# fpga-bank2-inside.net
KiCad netlist of a schematic drawn in Altium Designer
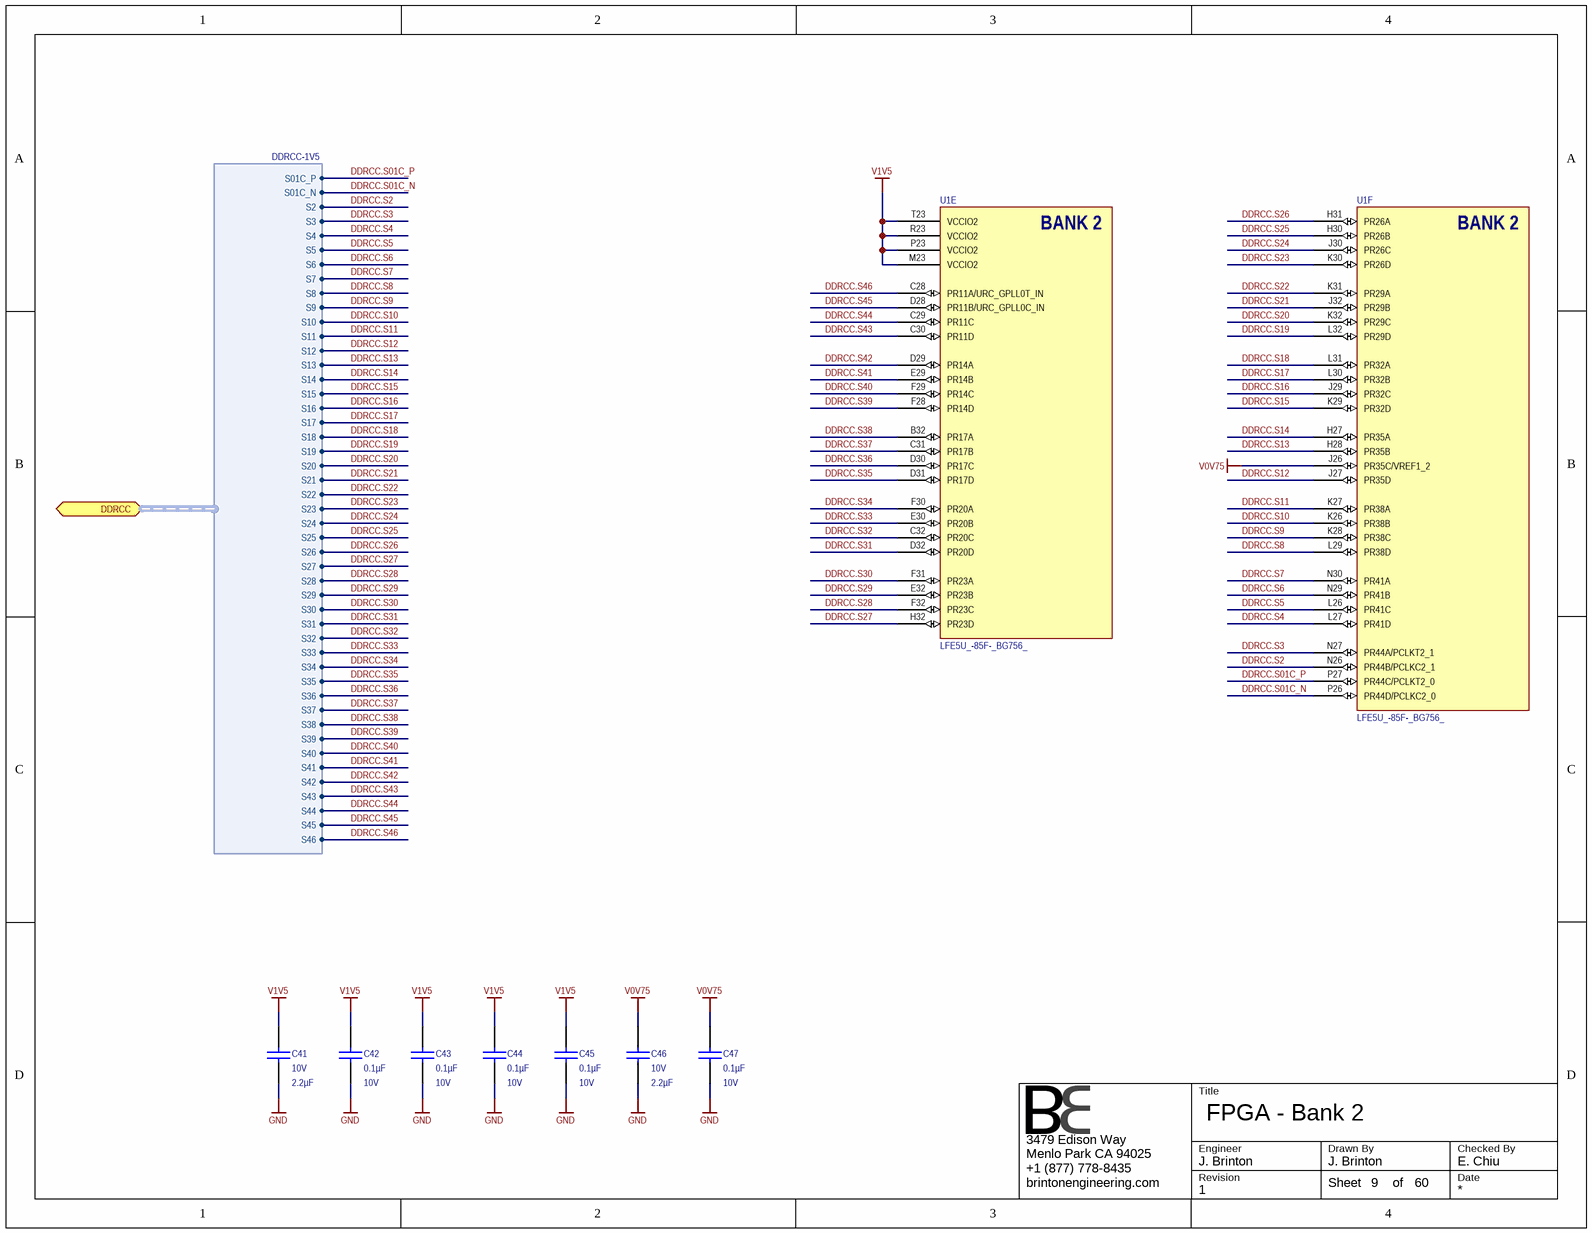
[diagram p0: fpga-bank2-inside.SchDoc]

(export (version "E")
  (design (tool "Eeschema 10.0.6"))
  (components
    (comp (ref "C41")
      (value "GRM188R71A225KE15D")
      (footprint "CAPC1608X90N")
      (description "CAP CER 2.2UF 10V 10% X7R 0603")
      (fields
        (field (name "MANUFACTURER") "Murata Electronics North America")
        (field (name "TOLERANCE") "±10%")
        (field (name "VOLTAGE - RATED") "10V")
        (field (name "CAPACITANCE") "2.2µF")
      )
      (libsource (lib "murata") (part "GRM188R71A225KE15D"))
    )
    (comp (ref "C42")
      (value "GRM155R71A104KA01J")
      (footprint "CAPC1005X56N")
      (description "CAP CER 0.1UF 10V 10% X7R 0402")
      (fields
        (field (name "MANUFACTURER") "Murata Electronics North America")
        (field (name "TOLERANCE") "±10%")
        (field (name "CAPACITANCE") "0.1µF")
        (field (name "VOLTAGE - RATED") "10V")
      )
      (libsource (lib "murata") (part "GRM155R71A104KA01J"))
    )
    (comp (ref "C43")
      (value "GRM155R71A104KA01J")
      (footprint "CAPC1005X56N")
      (description "CAP CER 0.1UF 10V 10% X7R 0402")
      (fields
        (field (name "MANUFACTURER") "Murata Electronics North America")
        (field (name "TOLERANCE") "±10%")
        (field (name "CAPACITANCE") "0.1µF")
        (field (name "VOLTAGE - RATED") "10V")
      )
      (libsource (lib "murata") (part "GRM155R71A104KA01J"))
    )
    (comp (ref "C44")
      (value "GRM155R71A104KA01J")
      (footprint "CAPC1005X56N")
      (description "CAP CER 0.1UF 10V 10% X7R 0402")
      (fields
        (field (name "MANUFACTURER") "Murata Electronics North America")
        (field (name "TOLERANCE") "±10%")
        (field (name "CAPACITANCE") "0.1µF")
        (field (name "VOLTAGE - RATED") "10V")
      )
      (libsource (lib "murata") (part "GRM155R71A104KA01J"))
    )
    (comp (ref "C45")
      (value "GRM155R71A104KA01J")
      (footprint "CAPC1005X56N")
      (description "CAP CER 0.1UF 10V 10% X7R 0402")
      (fields
        (field (name "MANUFACTURER") "Murata Electronics North America")
        (field (name "TOLERANCE") "±10%")
        (field (name "CAPACITANCE") "0.1µF")
        (field (name "VOLTAGE - RATED") "10V")
      )
      (libsource (lib "murata") (part "GRM155R71A104KA01J"))
    )
    (comp (ref "C46")
      (value "GRM188R71A225KE15D")
      (footprint "CAPC1608X90N")
      (description "CAP CER 2.2UF 10V 10% X7R 0603")
      (fields
        (field (name "MANUFACTURER") "Murata Electronics North America")
        (field (name "TOLERANCE") "±10%")
        (field (name "VOLTAGE - RATED") "10V")
        (field (name "CAPACITANCE") "2.2µF")
      )
      (libsource (lib "murata") (part "GRM188R71A225KE15D"))
    )
    (comp (ref "C47")
      (value "GRM155R71A104KA01J")
      (footprint "CAPC1005X56N")
      (description "CAP CER 0.1UF 10V 10% X7R 0402")
      (fields
        (field (name "MANUFACTURER") "Murata Electronics North America")
        (field (name "TOLERANCE") "±10%")
        (field (name "CAPACITANCE") "0.1µF")
        (field (name "VOLTAGE - RATED") "10V")
      )
      (libsource (lib "murata") (part "GRM155R71A104KA01J"))
    )
    (comp (ref "U1")
      (value "LFE5U_-85F-_BG756_")
      (footprint "lattice:caBGA756")
      (description "ECP5 FPGA, 85k LUT, 756-caBGA")
      (fields (field (name "MANUFACTURER") "Lattice Semiconductor"))
      (libsource (lib "lattice") (part "LFE5U_-85F-_BG756_"))
    )
  )
  (nets
    (net (code "2") (name "/DDRCC.S01C_N") (class "Default")
      (node (ref "U1") (pin "P26") (pinfunction "PR44D/PCLKC2_0_P26") (pintype "bidirectional"))
    )
    (net (code "3") (name "/DDRCC.S01C_P") (class "Default")
      (node (ref "U1") (pin "P27") (pinfunction "PR44C/PCLKT2_0_P27") (pintype "bidirectional"))
    )
    (net (code "4") (name "/DDRCC.S2") (class "Default")
      (node (ref "U1") (pin "N26") (pinfunction "PR44B/PCLKC2_1_N26") (pintype "bidirectional"))
    )
    (net (code "5") (name "/DDRCC.S3") (class "Default")
      (node (ref "U1") (pin "N27") (pinfunction "PR44A/PCLKT2_1_N27") (pintype "bidirectional"))
    )
    (net (code "6") (name "/DDRCC.S4") (class "Default")
      (node (ref "U1") (pin "L27") (pinfunction "PR41D_L27") (pintype "bidirectional"))
    )
    (net (code "7") (name "/DDRCC.S5") (class "Default")
      (node (ref "U1") (pin "L26") (pinfunction "PR41C_L26") (pintype "bidirectional"))
    )
    (net (code "8") (name "/DDRCC.S6") (class "Default")
      (node (ref "U1") (pin "N29") (pinfunction "PR41B_N29") (pintype "bidirectional"))
    )
    (net (code "9") (name "/DDRCC.S7") (class "Default")
      (node (ref "U1") (pin "N30") (pinfunction "PR41A_N30") (pintype "bidirectional"))
    )
    (net (code "10") (name "/DDRCC.S8") (class "Default")
      (node (ref "U1") (pin "L29") (pinfunction "PR38D_L29") (pintype "bidirectional"))
    )
    (net (code "11") (name "/DDRCC.S9") (class "Default")
      (node (ref "U1") (pin "K28") (pinfunction "PR38C_K28") (pintype "bidirectional"))
    )
    (net (code "12") (name "/DDRCC.S10") (class "Default")
      (node (ref "U1") (pin "K26") (pinfunction "PR38B_K26") (pintype "bidirectional"))
    )
    (net (code "13") (name "/DDRCC.S11") (class "Default")
      (node (ref "U1") (pin "K27") (pinfunction "PR38A_K27") (pintype "bidirectional"))
    )
    (net (code "14") (name "/DDRCC.S12") (class "Default")
      (node (ref "U1") (pin "J27") (pinfunction "PR35D_J27") (pintype "bidirectional"))
    )
    (net (code "15") (name "/DDRCC.S13") (class "Default")
      (node (ref "U1") (pin "H28") (pinfunction "PR35B_H28") (pintype "bidirectional"))
    )
    (net (code "16") (name "/DDRCC.S14") (class "Default")
      (node (ref "U1") (pin "H27") (pinfunction "PR35A_H27") (pintype "bidirectional"))
    )
    (net (code "17") (name "/DDRCC.S15") (class "Default")
      (node (ref "U1") (pin "K29") (pinfunction "PR32D_K29") (pintype "bidirectional"))
    )
    (net (code "18") (name "/DDRCC.S16") (class "Default")
      (node (ref "U1") (pin "J29") (pinfunction "PR32C_J29") (pintype "bidirectional"))
    )
    (net (code "19") (name "/DDRCC.S17") (class "Default")
      (node (ref "U1") (pin "L30") (pinfunction "PR32B_L30") (pintype "bidirectional"))
    )
    (net (code "20") (name "/DDRCC.S18") (class "Default")
      (node (ref "U1") (pin "L31") (pinfunction "PR32A_L31") (pintype "bidirectional"))
    )
    (net (code "21") (name "/DDRCC.S19") (class "Default")
      (node (ref "U1") (pin "L32") (pinfunction "PR29D_L32") (pintype "bidirectional"))
    )
    (net (code "22") (name "/DDRCC.S20") (class "Default")
      (node (ref "U1") (pin "K32") (pinfunction "PR29C_K32") (pintype "bidirectional"))
    )
    (net (code "23") (name "/DDRCC.S21") (class "Default")
      (node (ref "U1") (pin "J32") (pinfunction "PR29B_J32") (pintype "bidirectional"))
    )
    (net (code "24") (name "/DDRCC.S22") (class "Default")
      (node (ref "U1") (pin "K31") (pinfunction "PR29A_K31") (pintype "bidirectional"))
    )
    (net (code "25") (name "/DDRCC.S23") (class "Default")
      (node (ref "U1") (pin "K30") (pinfunction "PR26D_K30") (pintype "bidirectional"))
    )
    (net (code "26") (name "/DDRCC.S24") (class "Default")
      (node (ref "U1") (pin "J30") (pinfunction "PR26C_J30") (pintype "bidirectional"))
    )
    (net (code "27") (name "/DDRCC.S25") (class "Default")
      (node (ref "U1") (pin "H30") (pinfunction "PR26B_H30") (pintype "bidirectional"))
    )
    (net (code "28") (name "/DDRCC.S26") (class "Default")
      (node (ref "U1") (pin "H31") (pinfunction "PR26A_H31") (pintype "bidirectional"))
    )
    (net (code "29") (name "/DDRCC.S27") (class "Default")
      (node (ref "U1") (pin "H32") (pinfunction "PR23D_H32") (pintype "bidirectional"))
    )
    (net (code "30") (name "/DDRCC.S28") (class "Default")
      (node (ref "U1") (pin "F32") (pinfunction "PR23C_F32") (pintype "bidirectional"))
    )
    (net (code "31") (name "/DDRCC.S29") (class "Default")
      (node (ref "U1") (pin "E32") (pinfunction "PR23B_E32") (pintype "bidirectional"))
    )
    (net (code "32") (name "/DDRCC.S30") (class "Default")
      (node (ref "U1") (pin "F31") (pinfunction "PR23A_F31") (pintype "bidirectional"))
    )
    (net (code "33") (name "/DDRCC.S31") (class "Default")
      (node (ref "U1") (pin "D32") (pinfunction "PR20D_D32") (pintype "bidirectional"))
    )
    (net (code "34") (name "/DDRCC.S32") (class "Default")
      (node (ref "U1") (pin "C32") (pinfunction "PR20C_C32") (pintype "bidirectional"))
    )
    (net (code "35") (name "/DDRCC.S33") (class "Default")
      (node (ref "U1") (pin "E30") (pinfunction "PR20B_E30") (pintype "bidirectional"))
    )
    (net (code "36") (name "/DDRCC.S34") (class "Default")
      (node (ref "U1") (pin "F30") (pinfunction "PR20A_F30") (pintype "bidirectional"))
    )
    (net (code "37") (name "/DDRCC.S35") (class "Default")
      (node (ref "U1") (pin "D31") (pinfunction "PR17D_D31") (pintype "bidirectional"))
    )
    (net (code "38") (name "/DDRCC.S36") (class "Default")
      (node (ref "U1") (pin "D30") (pinfunction "PR17C_D30") (pintype "bidirectional"))
    )
    (net (code "39") (name "/DDRCC.S37") (class "Default")
      (node (ref "U1") (pin "C31") (pinfunction "PR17B_C31") (pintype "bidirectional"))
    )
    (net (code "40") (name "/DDRCC.S38") (class "Default")
      (node (ref "U1") (pin "B32") (pinfunction "PR17A_B32") (pintype "bidirectional"))
    )
    (net (code "41") (name "/DDRCC.S39") (class "Default")
      (node (ref "U1") (pin "F28") (pinfunction "PR14D_F28") (pintype "bidirectional"))
    )
    (net (code "42") (name "/DDRCC.S40") (class "Default")
      (node (ref "U1") (pin "F29") (pinfunction "PR14C_F29") (pintype "bidirectional"))
    )
    (net (code "43") (name "/DDRCC.S41") (class "Default")
      (node (ref "U1") (pin "E29") (pinfunction "PR14B_E29") (pintype "bidirectional"))
    )
    (net (code "44") (name "/DDRCC.S42") (class "Default")
      (node (ref "U1") (pin "D29") (pinfunction "PR14A_D29") (pintype "bidirectional"))
    )
    (net (code "45") (name "/DDRCC.S43") (class "Default")
      (node (ref "U1") (pin "C30") (pinfunction "PR11D_C30") (pintype "bidirectional"))
    )
    (net (code "46") (name "/DDRCC.S44") (class "Default")
      (node (ref "U1") (pin "C29") (pinfunction "PR11C_C29") (pintype "bidirectional"))
    )
    (net (code "47") (name "/DDRCC.S45") (class "Default")
      (node (ref "U1") (pin "D28") (pinfunction "PR11B/URC_GPLL0C_IN_D28") (pintype "bidirectional"))
    )
    (net (code "48") (name "/DDRCC.S46") (class "Default")
      (node (ref "U1") (pin "C28") (pinfunction "PR11A/URC_GPLL0T_IN_C28") (pintype "bidirectional"))
    )
    (net (code "50") (name "GND") (class "Default")
      (node (ref "C41") (pin "1") (pinfunction "1_1") (pintype "passive"))
      (node (ref "C42") (pin "1") (pinfunction "1_1") (pintype "passive"))
      (node (ref "C43") (pin "1") (pinfunction "1_1") (pintype "passive"))
      (node (ref "C44") (pin "1") (pinfunction "1_1") (pintype "passive"))
      (node (ref "C45") (pin "1") (pinfunction "1_1") (pintype "passive"))
      (node (ref "C46") (pin "1") (pinfunction "1_1") (pintype "passive"))
      (node (ref "C47") (pin "1") (pinfunction "1_1") (pintype "passive"))
    )
    (net (code "51") (name "V0V75") (class "Default")
      (node (ref "C46") (pin "2") (pinfunction "2_2") (pintype "passive"))
      (node (ref "C47") (pin "2") (pinfunction "2_2") (pintype "passive"))
      (node (ref "U1") (pin "J26") (pinfunction "PR35C/VREF1_2_J26") (pintype "bidirectional"))
    )
    (net (code "52") (name "V1V5") (class "Default")
      (node (ref "C41") (pin "2") (pinfunction "2_2") (pintype "passive"))
      (node (ref "C42") (pin "2") (pinfunction "2_2") (pintype "passive"))
      (node (ref "C43") (pin "2") (pinfunction "2_2") (pintype "passive"))
      (node (ref "C44") (pin "2") (pinfunction "2_2") (pintype "passive"))
      (node (ref "C45") (pin "2") (pinfunction "2_2") (pintype "passive"))
      (node (ref "U1") (pin "M23") (pinfunction "VCCIO2_M23") (pintype "power_in"))
      (node (ref "U1") (pin "P23") (pinfunction "VCCIO2_P23") (pintype "power_in"))
      (node (ref "U1") (pin "R23") (pinfunction "VCCIO2_R23") (pintype "power_in"))
      (node (ref "U1") (pin "T23") (pinfunction "VCCIO2_T23") (pintype "power_in"))
    )
  )
)
